# UPS_Charger_v1.net
KiCad netlist of a schematic drawn in Altium Designer
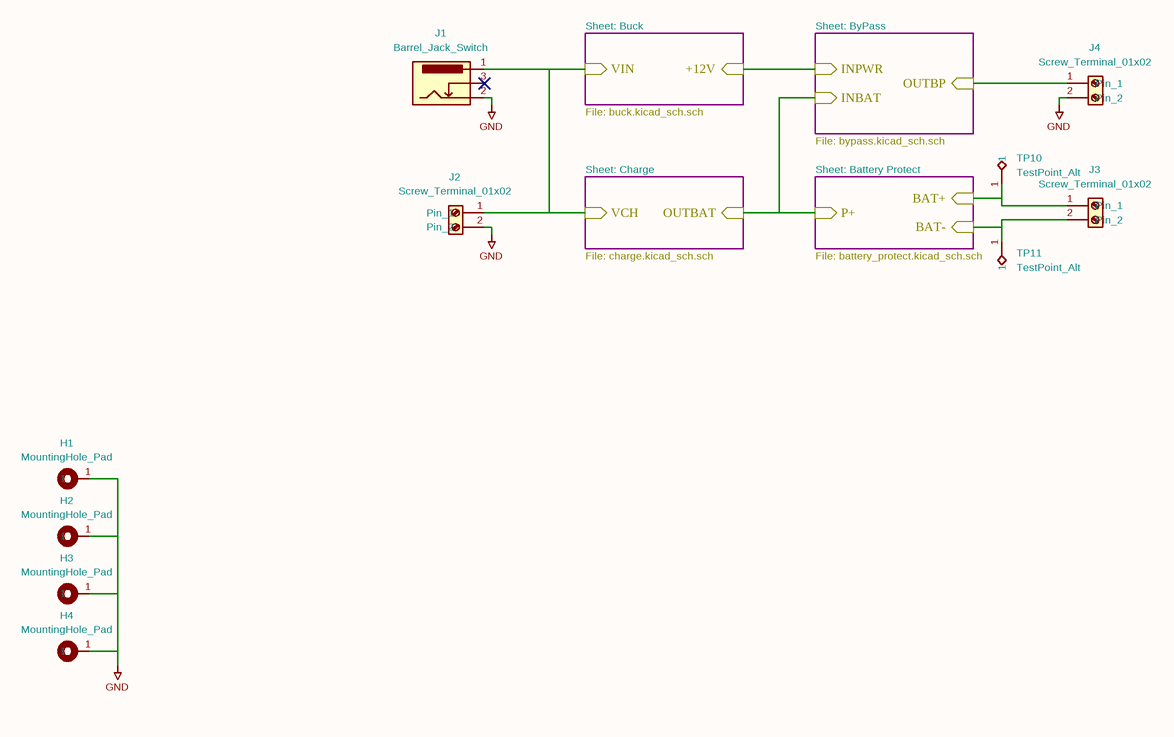
[diagram p0: UPS_Charger_v1.SchDoc]

(export (version "E")
  (design (tool "Eeschema 10.0.6"))
  (components
    (comp (ref "H1")
      (value "MountingHole_Pad")
      (description "Mounting Hole with connection")
      (libsource (lib "Mechanical") (part "MountingHole_Pad"))
    )
    (comp (ref "H2")
      (value "MountingHole_Pad")
      (description "Mounting Hole with connection")
      (libsource (lib "Mechanical") (part "MountingHole_Pad"))
    )
    (comp (ref "H3")
      (value "MountingHole_Pad")
      (description "Mounting Hole with connection")
      (libsource (lib "Mechanical") (part "MountingHole_Pad"))
    )
    (comp (ref "H4")
      (value "MountingHole_Pad")
      (description "Mounting Hole with connection")
      (libsource (lib "Mechanical") (part "MountingHole_Pad"))
    )
    (comp (ref "J1")
      (value "Barrel_Jack_Switch")
      (description "DC Barrel Jack with an internal switch")
      (libsource (lib "Connector") (part "Barrel_Jack_Switch"))
    )
    (comp (ref "J2") (value "Screw_Terminal_01x02") (libsource (lib "") (part "Screw_Terminal_01x02_1")))
    (comp (ref "J3")
      (value "Screw_Terminal_01x02")
      (libsource (lib "Connector") (part "Screw_Terminal_01x02"))
    )
    (comp (ref "J4")
      (value "Screw_Terminal_01x02")
      (libsource (lib "Connector") (part "Screw_Terminal_01x02"))
    )
    (comp (ref "TP10")
      (value "TestPoint_Alt")
      (description "test point (alternative shape)")
      (libsource (lib "Connector") (part "TestPoint_Alt"))
    )
    (comp (ref "TP11")
      (value "TestPoint_Alt")
      (description "test point (alternative shape)")
      (libsource (lib "Connector") (part "TestPoint_Alt"))
    )
  )
  (nets
    (net (code "2") (name "/BAT+") (class "Default")
      (node (ref "J3") (pin "1") (pinfunction "Pin_1_1") (pintype "passive"))
      (node (ref "TP10") (pin "1") (pinfunction "1_1") (pintype "passive"))
    )
    (net (code "3") (name "/BAT-") (class "Default")
      (node (ref "J3") (pin "2") (pinfunction "Pin_2_2") (pintype "passive"))
      (node (ref "TP11") (pin "1") (pinfunction "1_1") (pintype "passive"))
    )
    (net (code "5") (name "/OUTBP") (class "Default")
      (node (ref "J4") (pin "1") (pinfunction "Pin_1_1") (pintype "passive"))
    )
    (net (code "6") (name "/VCH") (class "Default")
      (node (ref "J1") (pin "1") (pinfunction "1_1") (pintype "passive"))
      (node (ref "J2") (pin "1") (pinfunction "Pin_1_1") (pintype "passive"))
    )
    (net (code "7") (name "GND") (class "Default")
      (node (ref "H1") (pin "1") (pinfunction "1_1") (pintype "passive"))
      (node (ref "H2") (pin "1") (pinfunction "1_1") (pintype "passive"))
      (node (ref "H3") (pin "1") (pinfunction "1_1") (pintype "passive"))
      (node (ref "H4") (pin "1") (pinfunction "1_1") (pintype "passive"))
      (node (ref "J1") (pin "2") (pinfunction "2_2") (pintype "passive"))
      (node (ref "J2") (pin "2") (pinfunction "Pin_2_2") (pintype "passive"))
      (node (ref "J4") (pin "2") (pinfunction "Pin_2_2") (pintype "passive"))
    )
    (net (code "8") (name "unconnected-(J1-Pad3)") (class "Default")
      (node (ref "J1") (pin "3") (pinfunction "3_3") (pintype "passive+no_connect"))
    )
  )
)
